# Guc.net
KiCad netlist of a schematic drawn in Altium Designer
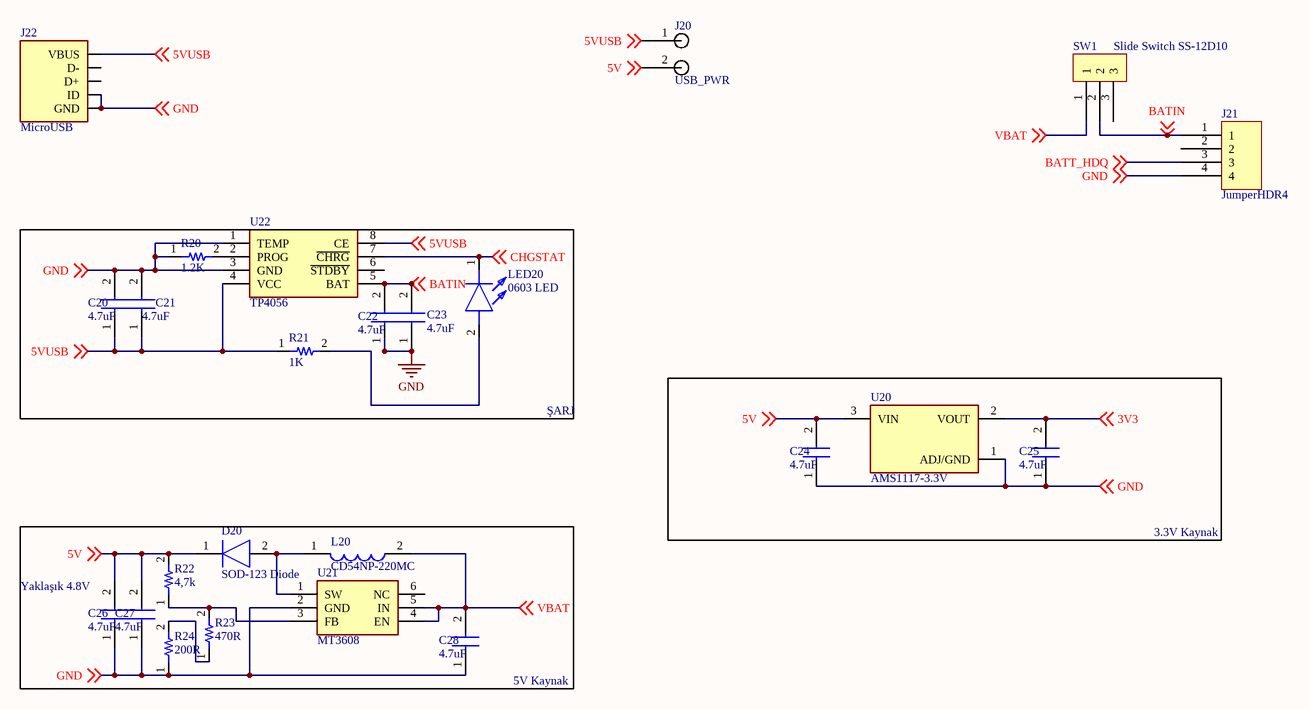
[diagram p0: Guc.SchDoc]

(export (version "E")
  (design (tool "Eeschema 10.0.6"))
  (components
    (comp (ref "C20")
      (value "4.7uF")
      (footprint "0603 Capacitor")
      (description "Capacitor")
      (fields
        (field (name "MANUFACTURER_PART_NUMBER") "06031A120JAT2A")
        (field (name "MOUSER PART NUMBER") "581-06031A120J")
      )
      (libsource (lib "uAltiumLib") (part "0603 Capacitor"))
    )
    (comp (ref "C21")
      (value "4.7uF")
      (footprint "0603 Capacitor")
      (description "Capacitor")
      (fields
        (field (name "MANUFACTURER_PART_NUMBER") "06031A120JAT2A")
        (field (name "MOUSER PART NUMBER") "581-06031A120J")
      )
      (libsource (lib "uAltiumLib") (part "0603 Capacitor"))
    )
    (comp (ref "C22")
      (value "4.7uF")
      (footprint "0603 Capacitor")
      (description "Capacitor")
      (fields
        (field (name "MANUFACTURER_PART_NUMBER") "06031A120JAT2A")
        (field (name "MOUSER PART NUMBER") "581-06031A120J")
      )
      (libsource (lib "uAltiumLib") (part "0603 Capacitor"))
    )
    (comp (ref "C23")
      (value "4.7uF")
      (footprint "0603 Capacitor")
      (description "Capacitor")
      (fields
        (field (name "MANUFACTURER_PART_NUMBER") "06031A120JAT2A")
        (field (name "MOUSER PART NUMBER") "581-06031A120J")
      )
      (libsource (lib "uAltiumLib") (part "0603 Capacitor"))
    )
    (comp (ref "C24")
      (value "4.7uF")
      (footprint "0603 Capacitor")
      (description "Capacitor")
      (fields
        (field (name "MANUFACTURER_PART_NUMBER") "06031A120JAT2A")
        (field (name "MOUSER PART NUMBER") "581-06031A120J")
      )
      (libsource (lib "uAltiumLib") (part "0603 Capacitor"))
    )
    (comp (ref "C25")
      (value "4.7uF")
      (footprint "0603 Capacitor")
      (description "Capacitor")
      (fields
        (field (name "MANUFACTURER_PART_NUMBER") "06031A120JAT2A")
        (field (name "MOUSER PART NUMBER") "581-06031A120J")
      )
      (libsource (lib "uAltiumLib") (part "0603 Capacitor"))
    )
    (comp (ref "C26")
      (value "4.7uF")
      (footprint "0603 Capacitor")
      (description "Capacitor")
      (fields
        (field (name "MANUFACTURER_PART_NUMBER") "06031A120JAT2A")
        (field (name "MOUSER PART NUMBER") "581-06031A120J")
      )
      (libsource (lib "uAltiumLib") (part "0603 Capacitor"))
    )
    (comp (ref "C27")
      (value "4.7uF")
      (footprint "0603 Capacitor")
      (description "Capacitor")
      (fields
        (field (name "MANUFACTURER_PART_NUMBER") "06031A120JAT2A")
        (field (name "MOUSER PART NUMBER") "581-06031A120J")
      )
      (libsource (lib "uAltiumLib") (part "0603 Capacitor"))
    )
    (comp (ref "C28")
      (value "4.7uF")
      (footprint "0603 Capacitor")
      (description "Capacitor")
      (fields
        (field (name "MANUFACTURER_PART_NUMBER") "06031A120JAT2A")
        (field (name "MOUSER PART NUMBER") "581-06031A120J")
      )
      (libsource (lib "uAltiumLib") (part "0603 Capacitor"))
    )
    (comp (ref "D20")
      (value "SOD-123 Diode")
      (footprint "SOD123")
      (description "Diode")
      (fields
        (field (name "MANUFACTURER_PART_NUMBER") "1N4148W-G3-08")
        (field (name "MOUSER PART NUMBER") "78-1N4148W-G3-08")
      )
      (libsource (lib "uAltiumLib") (part "SOD-123 Diode"))
    )
    (comp (ref "J20")
      (value "USB_PWR")
      (footprint "JumperHDR")
      (libsource (lib "uAltiumLib") (part "JumperHDR_ALT"))
    )
    (comp (ref "J21")
      (value "JumperHDR4")
      (footprint "JumperHDR4")
      (libsource (lib "uAltiumLib") (part "JumperHDR4"))
    )
    (comp (ref "J22")
      (value "MicroUSB")
      (footprint "MicroUSB")
      (fields (field (name "MP") "ZX62-B-5PA") (field (name "MF") "Hirose"))
      (libsource (lib "uAltiumLib") (part "MicroUSB"))
    )
    (comp (ref "L20")
      (value "CD54NP-220MC")
      (footprint "SamacSys:CD54NP220MC")
      (description "Inductor")
      (fields (field (name "MOUSER PART NUMBER") "851-CD54NP-220MC"))
      (libsource (lib "SamacSys") (part "CD54NP-220MC"))
    )
    (comp (ref "LED20")
      (value "0603 LED")
      (footprint "0603 LED")
      (description "LED")
      (fields
        (field (name "MANUFACTURER_PART_NUMBER") "150060GS55040")
        (field (name "MOUSER PART NUMBER") "710-150060GS55040")
      )
      (libsource (lib "uAltiumLib") (part "0603 LED"))
    )
    (comp (ref "R20")
      (value "1.2K")
      (footprint "0603 Resistor")
      (description "Resistor")
      (fields
        (field (name "MANUFACTURER_PART_NUMBER") "CPF0603B100RE1")
        (field (name "MOUSER PART NUMBER") "279-CPF0603B100RE1")
      )
      (libsource (lib "uAltiumLib") (part "0603 Resistor"))
    )
    (comp (ref "R21")
      (value "1K")
      (footprint "0603 Resistor")
      (description "Resistor")
      (fields
        (field (name "MANUFACTURER_PART_NUMBER") "CPF0603B100RE1")
        (field (name "MOUSER PART NUMBER") "279-CPF0603B100RE1")
      )
      (libsource (lib "uAltiumLib") (part "0603 Resistor"))
    )
    (comp (ref "R22")
      (value "4,7k")
      (footprint "0603 Resistor")
      (description "Resistor")
      (fields
        (field (name "MANUFACTURER_PART_NUMBER") "CPF0603B100RE1")
        (field (name "MOUSER PART NUMBER") "279-CPF0603B100RE1")
      )
      (libsource (lib "uAltiumLib") (part "0603 Resistor"))
    )
    (comp (ref "R23")
      (value "470R")
      (footprint "0603 Resistor")
      (description "Resistor")
      (fields
        (field (name "MANUFACTURER_PART_NUMBER") "CPF0603B100RE1")
        (field (name "MOUSER PART NUMBER") "279-CPF0603B100RE1")
      )
      (libsource (lib "uAltiumLib") (part "0603 Resistor"))
    )
    (comp (ref "R24")
      (value "200R")
      (footprint "0603 Resistor")
      (description "Resistor")
      (fields
        (field (name "MANUFACTURER_PART_NUMBER") "CPF0603B100RE1")
        (field (name "MOUSER PART NUMBER") "279-CPF0603B100RE1")
      )
      (libsource (lib "uAltiumLib") (part "0603 Resistor"))
    )
    (comp (ref "SW1")
      (value "Slide Switch SS-12D10")
      (footprint "Slide Switch ss12d10")
      (libsource (lib "uAltiumLib") (part "Slide Switch SS-12D10"))
    )
    (comp (ref "U20")
      (value "AMS1117-3.3V")
      (footprint "AMS1117_SOT223")
      (fields (field (name "MP") "AMS1117") (field (name "MF") "Seeed Technology"))
      (libsource (lib "uAltiumLib") (part "AMS1117"))
    )
    (comp (ref "U21")
      (value "MT3608")
      (footprint "MT3608")
      (description "Undefined or Miscellaneous")
      (libsource (lib "uAltiumLib") (part "MT3608"))
    )
    (comp (ref "U22")
      (value "TP4056")
      (footprint "TP4056A")
      (description "Connector")
      (libsource (lib "uAltiumLib") (part "TP4056"))
    )
  )
  (nets
    (net (code "1") (name "3V3") (class "Default")
      (node (ref "C25") (pin "2") (pinfunction "2_2") (pintype "passive"))
      (node (ref "U20") (pin "2") (pinfunction "VOUT_2") (pintype "passive"))
    )
    (net (code "2") (name "5V") (class "Default")
      (node (ref "C24") (pin "2") (pinfunction "2_2") (pintype "passive"))
      (node (ref "C26") (pin "2") (pinfunction "2_2") (pintype "passive"))
      (node (ref "C27") (pin "2") (pinfunction "2_2") (pintype "passive"))
      (node (ref "D20") (pin "1") (pinfunction "K_1") (pintype "passive"))
      (node (ref "J20") (pin "2") (pinfunction "2_2") (pintype "passive"))
      (node (ref "R22") (pin "2") (pinfunction "2_2") (pintype "passive"))
      (node (ref "U20") (pin "3") (pinfunction "VIN_3") (pintype "passive"))
    )
    (net (code "3") (name "5VUSB") (class "Default")
      (node (ref "C20") (pin "1") (pinfunction "1_1") (pintype "passive"))
      (node (ref "C21") (pin "1") (pinfunction "1_1") (pintype "passive"))
      (node (ref "J20") (pin "1") (pinfunction "1_1") (pintype "passive"))
      (node (ref "J22") (pin "1") (pinfunction "VBUS_1") (pintype "power_in"))
      (node (ref "R21") (pin "1") (pinfunction "1_1") (pintype "passive"))
      (node (ref "U22") (pin "4") (pinfunction "VCC_4") (pintype "passive"))
      (node (ref "U22") (pin "8") (pinfunction "CE_8") (pintype "passive"))
    )
    (net (code "4") (name "BATIN") (class "Default")
      (node (ref "C22") (pin "2") (pinfunction "2_2") (pintype "passive"))
      (node (ref "C23") (pin "2") (pinfunction "2_2") (pintype "passive"))
      (node (ref "J21") (pin "1") (pinfunction "1_1") (pintype "passive"))
      (node (ref "SW1") (pin "2") (pinfunction "2_2") (pintype "passive"))
      (node (ref "U22") (pin "5") (pinfunction "BAT_5") (pintype "passive"))
    )
    (net (code "5") (name "BATT_HDQ") (class "Default")
      (node (ref "J21") (pin "3") (pinfunction "3_3") (pintype "passive"))
    )
    (net (code "6") (name "CHGSTAT") (class "Default")
      (node (ref "LED20") (pin "1") (pinfunction "K_1") (pintype "passive"))
      (node (ref "U22") (pin "7") (pinfunction "~{CHRG}_7") (pintype "passive"))
    )
    (net (code "7") (name "GND") (class "Default")
      (node (ref "C20") (pin "2") (pinfunction "2_2") (pintype "passive"))
      (node (ref "C21") (pin "2") (pinfunction "2_2") (pintype "passive"))
      (node (ref "C22") (pin "1") (pinfunction "1_1") (pintype "passive"))
      (node (ref "C23") (pin "1") (pinfunction "1_1") (pintype "passive"))
      (node (ref "C24") (pin "1") (pinfunction "1_1") (pintype "passive"))
      (node (ref "C25") (pin "1") (pinfunction "1_1") (pintype "passive"))
      (node (ref "C26") (pin "1") (pinfunction "1_1") (pintype "passive"))
      (node (ref "C27") (pin "1") (pinfunction "1_1") (pintype "passive"))
      (node (ref "C28") (pin "1") (pinfunction "1_1") (pintype "passive"))
      (node (ref "J21") (pin "4") (pinfunction "4_4") (pintype "passive"))
      (node (ref "J22") (pin "4") (pinfunction "ID_4") (pintype "passive"))
      (node (ref "J22") (pin "5") (pinfunction "GND_5") (pintype "power_in"))
      (node (ref "R20") (pin "1") (pinfunction "1_1") (pintype "passive"))
      (node (ref "R24") (pin "1") (pinfunction "1_1") (pintype "passive"))
      (node (ref "U20") (pin "1") (pinfunction "ADJ/GND_1") (pintype "power_in"))
      (node (ref "U21") (pin "2") (pinfunction "GND_2") (pintype "passive"))
      (node (ref "U22") (pin "1") (pinfunction "TEMP_1") (pintype "passive"))
      (node (ref "U22") (pin "3") (pinfunction "GND_3") (pintype "passive"))
    )
    (net (code "8") (name "Net-(D20-A)") (class "Default")
      (node (ref "D20") (pin "2") (pinfunction "A_2") (pintype "passive"))
      (node (ref "L20") (pin "1") (pinfunction "1_1") (pintype "passive"))
      (node (ref "U21") (pin "1") (pinfunction "SW_1") (pintype "passive"))
    )
    (net (code "9") (name "Net-(LED20-A)") (class "Default")
      (node (ref "LED20") (pin "2") (pinfunction "A_2") (pintype "passive"))
      (node (ref "R21") (pin "2") (pinfunction "2_2") (pintype "passive"))
    )
    (net (code "10") (name "Net-(R23-Pad1)") (class "Default")
      (node (ref "R23") (pin "1") (pinfunction "1_1") (pintype "passive"))
      (node (ref "R24") (pin "2") (pinfunction "2_2") (pintype "passive"))
    )
    (net (code "11") (name "Net-(U21-FB)") (class "Default")
      (node (ref "R22") (pin "1") (pinfunction "1_1") (pintype "passive"))
      (node (ref "R23") (pin "2") (pinfunction "2_2") (pintype "passive"))
      (node (ref "U21") (pin "3") (pinfunction "FB_3") (pintype "passive"))
    )
    (net (code "12") (name "Net-(U22-PROG)") (class "Default")
      (node (ref "R20") (pin "2") (pinfunction "2_2") (pintype "passive"))
      (node (ref "U22") (pin "2") (pinfunction "PROG_2") (pintype "passive"))
    )
    (net (code "13") (name "VBAT") (class "Default")
      (node (ref "C28") (pin "2") (pinfunction "2_2") (pintype "passive"))
      (node (ref "L20") (pin "2") (pinfunction "2_2") (pintype "passive"))
      (node (ref "SW1") (pin "1") (pinfunction "1_1") (pintype "passive"))
      (node (ref "U21") (pin "4") (pinfunction "EN_4") (pintype "passive"))
      (node (ref "U21") (pin "5") (pinfunction "IN_5") (pintype "passive"))
    )
    (net (code "14") (name "unconnected-(J21-Pad2)") (class "Default")
      (node (ref "J21") (pin "2") (pinfunction "2_2") (pintype "passive"))
    )
    (net (code "15") (name "unconnected-(J22-D+-Pad3)") (class "Default")
      (node (ref "J22") (pin "3") (pinfunction "D+_3") (pintype "passive"))
    )
    (net (code "16") (name "unconnected-(J22-D--Pad2)") (class "Default")
      (node (ref "J22") (pin "2") (pinfunction "D-_2") (pintype "passive"))
    )
    (net (code "17") (name "unconnected-(SW1-Pad3)") (class "Default")
      (node (ref "SW1") (pin "3") (pinfunction "3_3") (pintype "passive"))
    )
    (net (code "18") (name "unconnected-(U21-NC-Pad6)") (class "Default")
      (node (ref "U21") (pin "6") (pinfunction "NC_6") (pintype "passive"))
    )
    (net (code "19") (name "unconnected-(U22-~{STDBY}-Pad6)") (class "Default")
      (node (ref "U22") (pin "6") (pinfunction "~{STDBY}_6") (pintype "passive"))
    )
  )
)
